# 130817_I_T_V_AriloRX_0_0.net
KiCad netlist of a schematic drawn in EAGLE
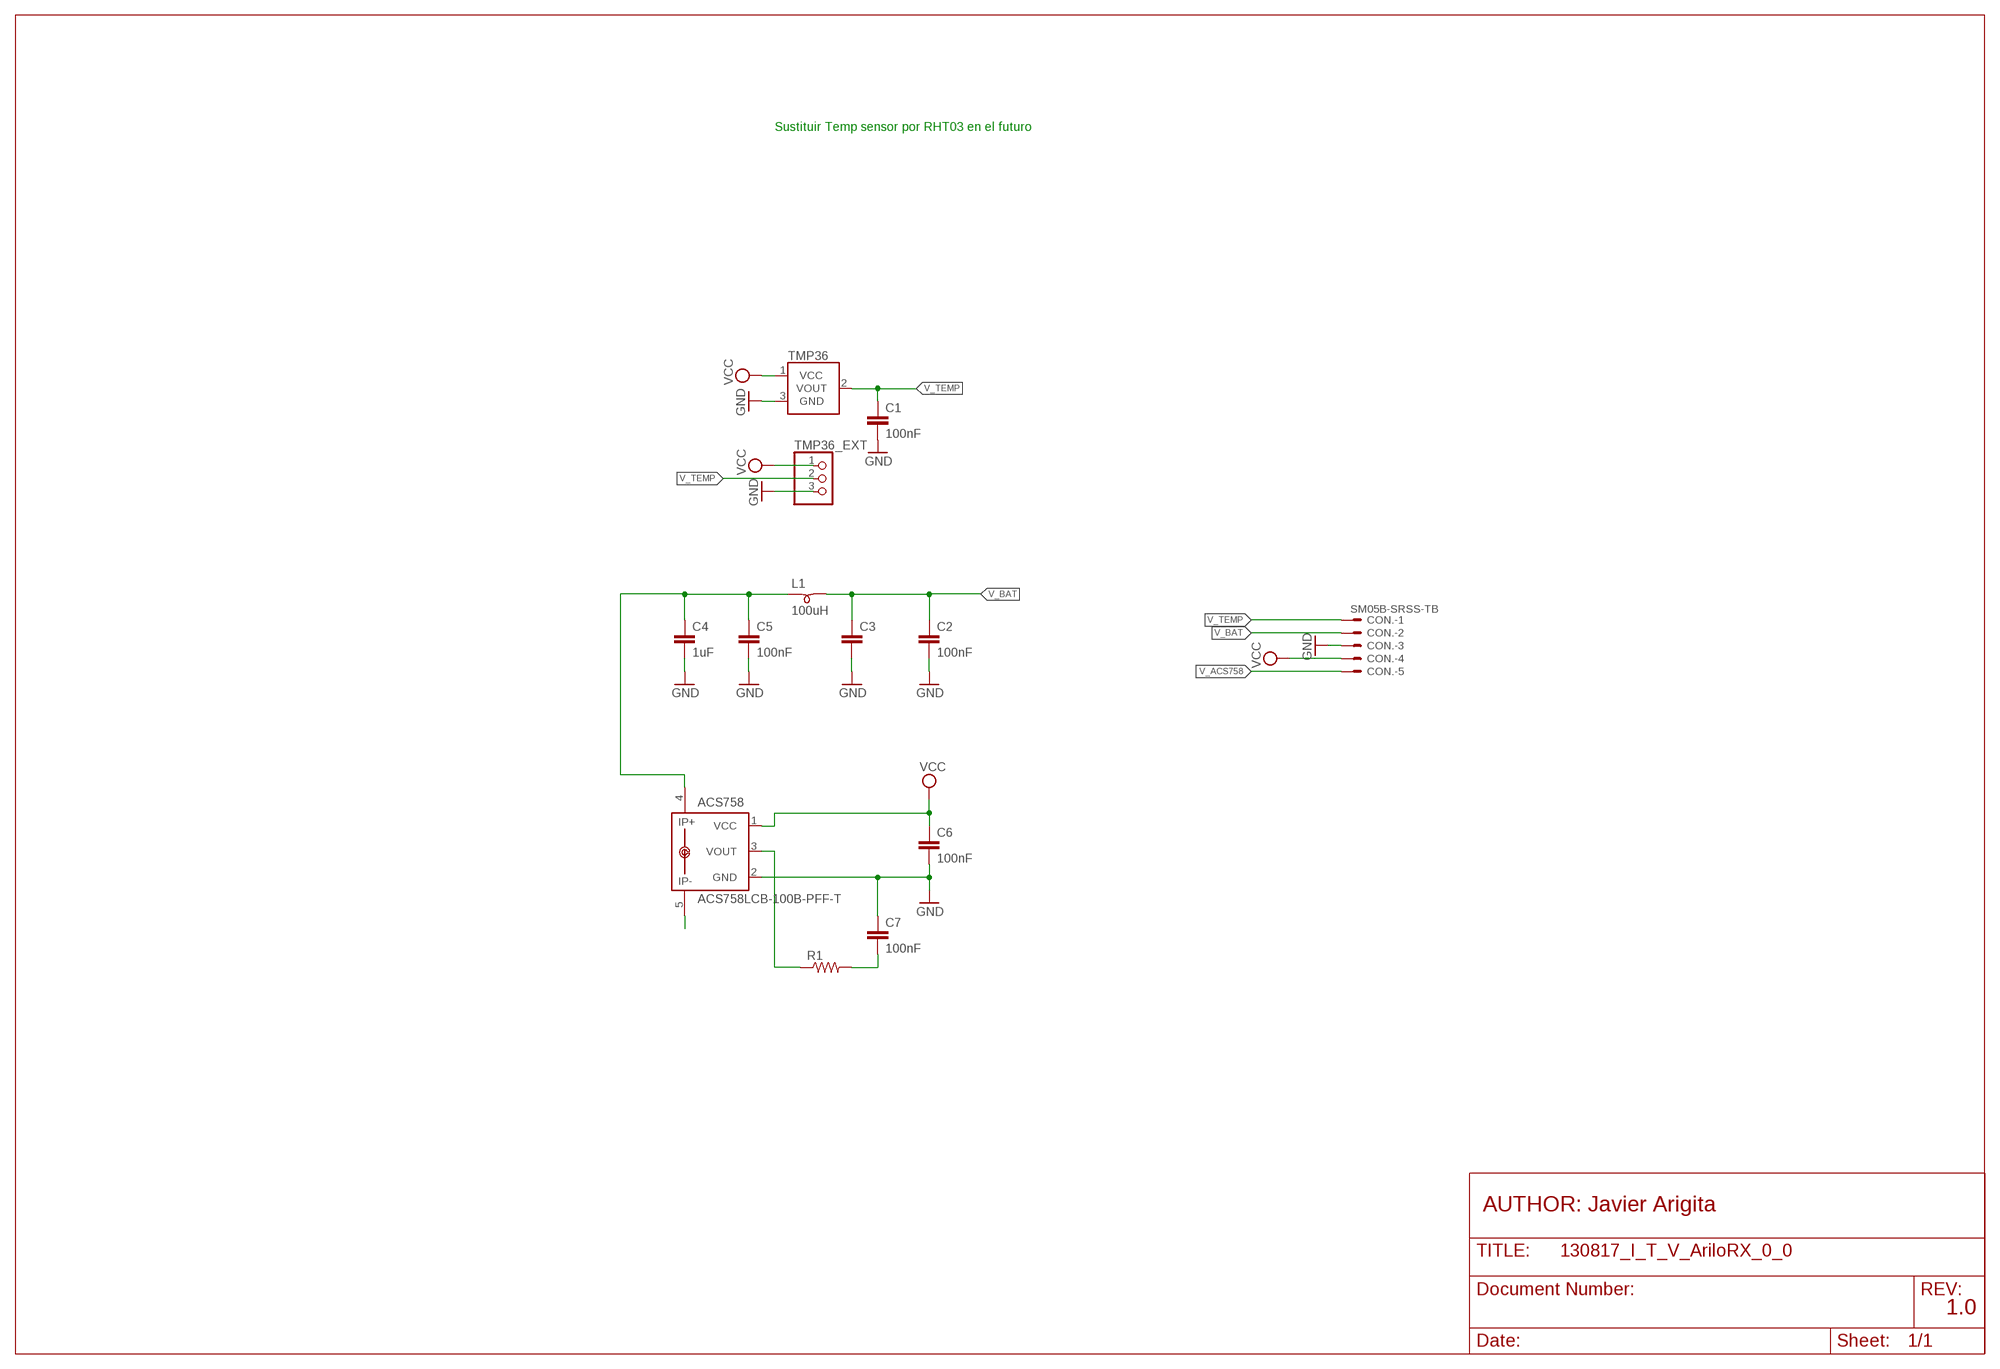
[diagram p0: schematic, sheet 1]

(export (version "E")
  (design (tool "Eeschema 10.0.6"))
  (components
    (comp (ref "ACS758")
      (value "ACS758LCB-100B-PFF-T")
      (footprint "eagle-import:CB-PFF")
      (libsource (lib "eagle-import") (part "ACS758LCB-100B-PFF-T"))
    )
    (comp (ref "C1")
      (value "100nF")
      (footprint "eagle-import:C0805")
      (libsource (lib "eagle-import") (part "C-EUC0805"))
    )
    (comp (ref "C2")
      (value "100nF")
      (footprint "eagle-import:C0805")
      (libsource (lib "eagle-import") (part "C-EUC0805"))
    )
    (comp (ref "C3")
      (value "C-EUC3216")
      (footprint "eagle-import:C3216")
      (libsource (lib "eagle-import") (part "C-EUC3216"))
    )
    (comp (ref "C4")
      (value "1uF")
      (footprint "eagle-import:C3216")
      (libsource (lib "eagle-import") (part "C-EUC3216"))
    )
    (comp (ref "C5")
      (value "100nF")
      (footprint "eagle-import:C0805")
      (libsource (lib "eagle-import") (part "C-EUC0805"))
    )
    (comp (ref "C6")
      (value "100nF")
      (footprint "eagle-import:C0805")
      (libsource (lib "eagle-import") (part "C-EUC0805"))
    )
    (comp (ref "C7")
      (value "100nF")
      (footprint "eagle-import:C0805")
      (libsource (lib "eagle-import") (part "C-EUC0805"))
    )
    (comp (ref "CON.")
      (value "SM05B-SRSS-TB")
      (footprint "eagle-import:SM05B-SRSS-TB")
      (libsource (lib "eagle-import") (part "?M05B-SRSS-TBS"))
    )
    (comp (ref "L1")
      (value "100uH")
      (footprint "eagle-import:SM-B5")
      (libsource (lib "eagle-import") (part "SM-B5"))
    )
    (comp (ref "R1")
      (value "RESISTOR0805")
      (footprint "eagle-import:R0805")
      (libsource (lib "eagle-import") (part "RESISTOR0805"))
    )
    (comp (ref "TMP36")
      (value "TMP36GT9")
      (footprint "eagle-import:TO-92")
      (libsource (lib "eagle-import") (part "TMP36GT9"))
    )
    (comp (ref "TMP36_EXT")
      (value "PINHD-1X3")
      (footprint "eagle-import:1X03")
      (libsource (lib "eagle-import") (part "PINHD-1X3"))
    )
  )
  (nets
    (net (code "1") (name "GND") (class "Default")
      (node (ref "ACS758") (pin "2") (pinfunction "GND_2") (pintype "power_in"))
      (node (ref "C1") (pin "2") (pinfunction "2_2") (pintype "passive"))
      (node (ref "C2") (pin "2") (pinfunction "2_2") (pintype "passive"))
      (node (ref "C3") (pin "2") (pinfunction "2_2") (pintype "passive"))
      (node (ref "C4") (pin "2") (pinfunction "2_2") (pintype "passive"))
      (node (ref "C5") (pin "2") (pinfunction "2_2") (pintype "passive"))
      (node (ref "C6") (pin "2") (pinfunction "2_2") (pintype "passive"))
      (node (ref "C7") (pin "1") (pinfunction "1_1") (pintype "passive"))
      (node (ref "CON.") (pin "3") (pinfunction "S_3") (pintype "passive"))
      (node (ref "TMP36") (pin "3") (pinfunction "GND_3") (pintype "bidirectional"))
      (node (ref "TMP36_EXT") (pin "3") (pinfunction "3_3") (pintype "passive"))
    )
    (net (code "2") (name "Net-(ACS758-IP+)") (class "Default")
      (node (ref "ACS758") (pin "4") (pinfunction "IP+_4") (pintype "passive"))
      (node (ref "C4") (pin "1") (pinfunction "1_1") (pintype "passive"))
      (node (ref "C5") (pin "1") (pinfunction "1_1") (pintype "passive"))
      (node (ref "L1") (pin "1") (pinfunction "1_1") (pintype "passive"))
    )
    (net (code "3") (name "Net-(ACS758-VOUT)") (class "Default")
      (node (ref "ACS758") (pin "3") (pinfunction "VOUT_3") (pintype "output"))
      (node (ref "R1") (pin "1") (pinfunction "1_1") (pintype "passive"))
    )
    (net (code "4") (name "Net-(C7-Pad2)") (class "Default")
      (node (ref "C7") (pin "2") (pinfunction "2_2") (pintype "passive"))
      (node (ref "R1") (pin "2") (pinfunction "2_2") (pintype "passive"))
    )
    (net (code "5") (name "VCC") (class "Default")
      (node (ref "ACS758") (pin "1") (pinfunction "VCC_1") (pintype "power_in"))
      (node (ref "C6") (pin "1") (pinfunction "1_1") (pintype "passive"))
      (node (ref "CON.") (pin "4") (pinfunction "S_4") (pintype "passive"))
      (node (ref "TMP36") (pin "1") (pinfunction "VCC_1") (pintype "bidirectional"))
      (node (ref "TMP36_EXT") (pin "1") (pinfunction "1_1") (pintype "passive"))
    )
    (net (code "6") (name "V_ACS758") (class "Default")
      (node (ref "CON.") (pin "5") (pinfunction "S_5") (pintype "passive"))
    )
    (net (code "7") (name "V_BAT") (class "Default")
      (node (ref "C2") (pin "1") (pinfunction "1_1") (pintype "passive"))
      (node (ref "C3") (pin "1") (pinfunction "1_1") (pintype "passive"))
      (node (ref "CON.") (pin "2") (pinfunction "S_2") (pintype "passive"))
      (node (ref "L1") (pin "2") (pinfunction "2_2") (pintype "passive"))
    )
    (net (code "8") (name "V_TEMP") (class "Default")
      (node (ref "C1") (pin "1") (pinfunction "1_1") (pintype "passive"))
      (node (ref "CON.") (pin "1") (pinfunction "S_1") (pintype "passive"))
      (node (ref "TMP36") (pin "2") (pinfunction "VOUT_2") (pintype "bidirectional"))
      (node (ref "TMP36_EXT") (pin "2") (pinfunction "2_2") (pintype "passive"))
    )
    (net (code "9") (name "unconnected-(ACS758-IP--Pad5)") (class "Default")
      (node (ref "ACS758") (pin "5") (pinfunction "IP-_5") (pintype "passive"))
    )
    (net (code "10") (name "unconnected-(ACS758-PadIP+1)") (class "Default")
      (node (ref "ACS758") (pin "IP+1") (pinfunction "IP+1_IP+1") (pintype "input"))
    )
    (net (code "11") (name "unconnected-(ACS758-PadIP-1)") (class "Default")
      (node (ref "ACS758") (pin "IP-1") (pinfunction "IP-1_IP-1") (pintype "input"))
    )
  )
)
